# relayOut.net
KiCad netlist of a schematic drawn in Altium Designer
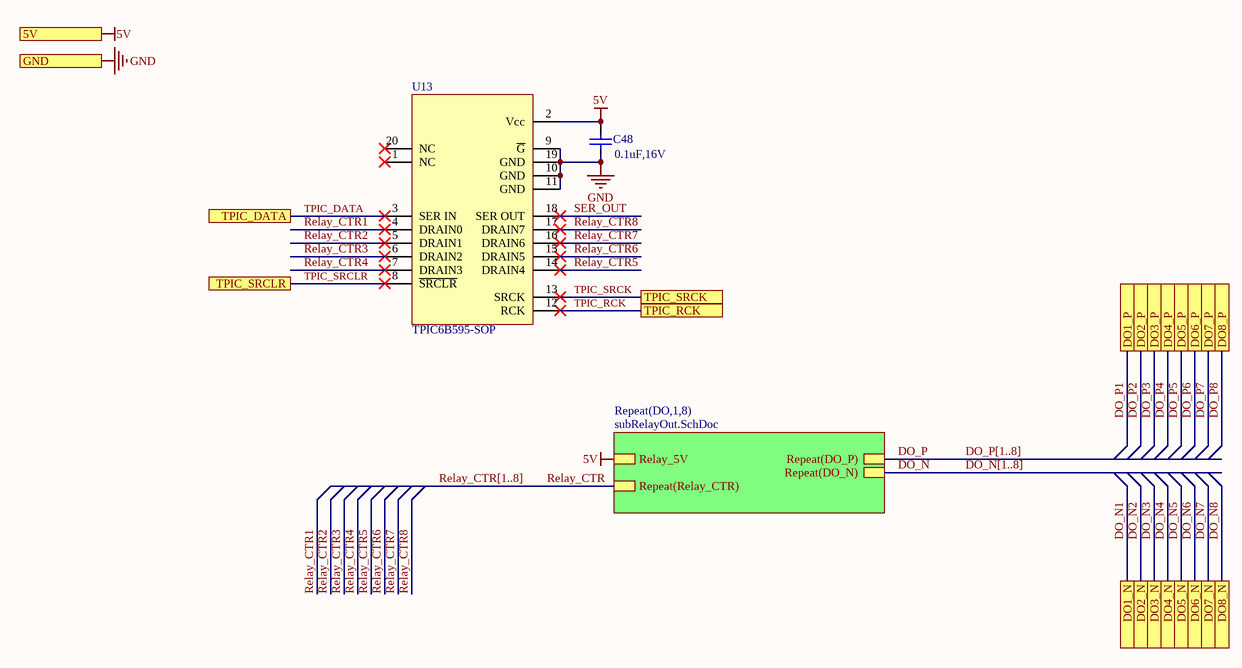
[diagram p0: relayOut.SchDoc]

(export (version "E")
  (design (tool "Eeschema 10.0.6"))
  (components
    (comp (ref "C48")
      (value "0.1uF,16V")
      (footprint "C0603")
      (description "无极电容")
      (libsource (lib "散件") (part "无极电容"))
    )
    (comp (ref "U13")
      (value "TPIC6B595-SOP")
      (footprint "TPIC6B595")
      (libsource (lib "*") (part "TPIC6B595"))
    )
  )
  (nets
    (net (code "22") (name "/Relay_CTR1") (class "Default")
      (node (ref "U13") (pin "4") (pinfunction "DRAIN0_4") (pintype "passive+no_connect"))
    )
    (net (code "23") (name "/Relay_CTR2") (class "Default")
      (node (ref "U13") (pin "5") (pinfunction "DRAIN1_5") (pintype "passive+no_connect"))
    )
    (net (code "24") (name "/Relay_CTR3") (class "Default")
      (node (ref "U13") (pin "6") (pinfunction "DRAIN2_6") (pintype "passive+no_connect"))
    )
    (net (code "25") (name "/Relay_CTR4") (class "Default")
      (node (ref "U13") (pin "7") (pinfunction "DRAIN3_7") (pintype "passive+no_connect"))
    )
    (net (code "26") (name "/Relay_CTR5") (class "Default")
      (node (ref "U13") (pin "14") (pinfunction "DRAIN4_14") (pintype "passive"))
    )
    (net (code "27") (name "/Relay_CTR6") (class "Default")
      (node (ref "U13") (pin "15") (pinfunction "DRAIN5_15") (pintype "passive"))
    )
    (net (code "28") (name "/Relay_CTR7") (class "Default")
      (node (ref "U13") (pin "16") (pinfunction "DRAIN6_16") (pintype "passive"))
    )
    (net (code "29") (name "/Relay_CTR8") (class "Default")
      (node (ref "U13") (pin "17") (pinfunction "DRAIN7_17") (pintype "passive"))
    )
    (net (code "31") (name "/SER_OUT") (class "Default")
      (node (ref "U13") (pin "18") (pinfunction "SER_OUT_18") (pintype "passive+no_connect"))
    )
    (net (code "32") (name "/TPIC_DATA") (class "Default")
      (node (ref "U13") (pin "3") (pinfunction "SER_IN_3") (pintype "passive+no_connect"))
    )
    (net (code "33") (name "/TPIC_RCK") (class "Default")
      (node (ref "U13") (pin "12") (pinfunction "RCK_12") (pintype "passive+no_connect"))
    )
    (net (code "34") (name "/TPIC_SRCK") (class "Default")
      (node (ref "U13") (pin "13") (pinfunction "SRCK_13") (pintype "passive+no_connect"))
    )
    (net (code "35") (name "/TPIC_SRCLR") (class "Default")
      (node (ref "U13") (pin "8") (pinfunction "~{SRCLR}_8") (pintype "passive+no_connect"))
    )
    (net (code "36") (name "5V") (class "Default")
      (node (ref "C48") (pin "2") (pinfunction "2_2") (pintype "passive"))
      (node (ref "U13") (pin "2") (pinfunction "Vcc_2") (pintype "passive"))
    )
    (net (code "37") (name "GND") (class "Default")
      (node (ref "C48") (pin "1") (pinfunction "1_1") (pintype "passive"))
      (node (ref "U13") (pin "10") (pinfunction "GND_10") (pintype "passive"))
      (node (ref "U13") (pin "11") (pinfunction "GND_11") (pintype "passive"))
      (node (ref "U13") (pin "19") (pinfunction "GND_19") (pintype "passive"))
      (node (ref "U13") (pin "9") (pinfunction "~{G}_9") (pintype "passive"))
    )
    (net (code "38") (name "unconnected-(U13-NC-Pad1)") (class "Default")
      (node (ref "U13") (pin "1") (pinfunction "NC_1") (pintype "passive+no_connect"))
    )
    (net (code "39") (name "unconnected-(U13-NC-Pad20)") (class "Default")
      (node (ref "U13") (pin "20") (pinfunction "NC_20") (pintype "passive+no_connect"))
    )
  )
)
